# RTC-Power-Eth.net
KiCad netlist of a schematic drawn in Altium Designer
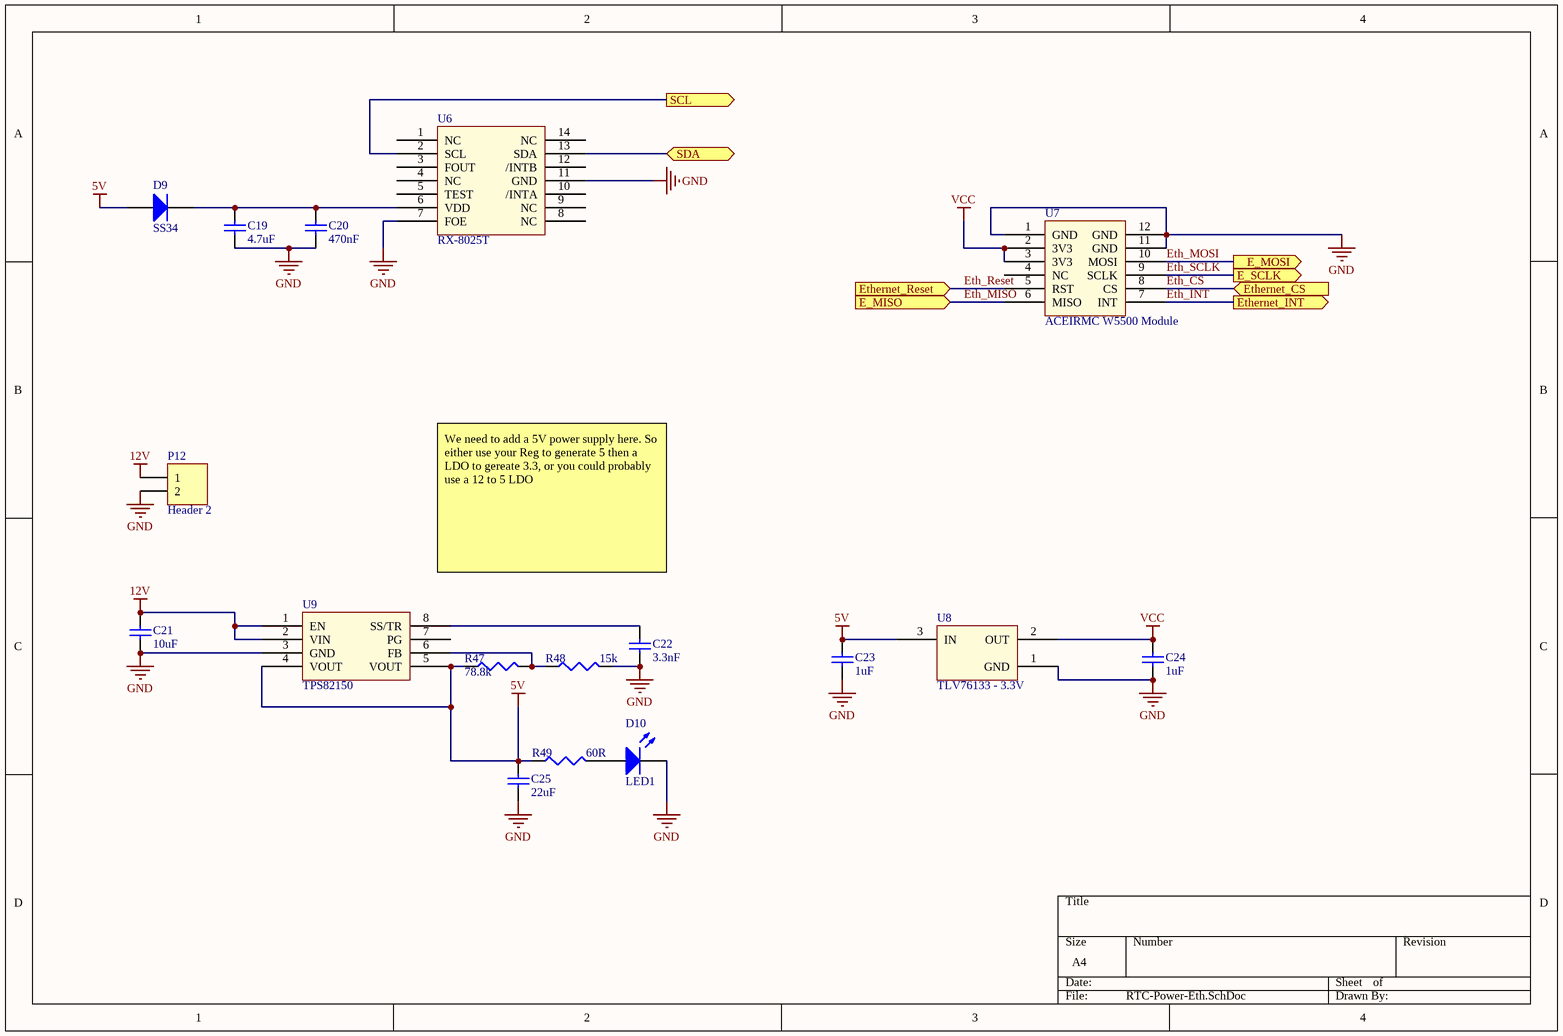
[diagram p0: RTC-Power-Eth.SchDoc]

(export (version "E")
  (design (tool "Eeschema 10.0.6"))
  (components
    (comp (ref "C19")
      (value "4.7uF")
      (footprint "CAPC2012X04M")
      (description "Capacitor")
      (fields (field (name "Comment") "Cap") (field (name "PUBLISHER") "Altium Limited"))
      (libsource (lib "Miscellaneous Devices") (part "Cap"))
    )
    (comp (ref "C20")
      (value "470nF")
      (footprint "CAPC2012X04M")
      (description "Capacitor")
      (fields (field (name "Comment") "Cap") (field (name "PUBLISHER") "Altium Limited"))
      (libsource (lib "Miscellaneous Devices") (part "Cap"))
    )
    (comp (ref "C21")
      (value "10uF")
      (footprint "CAPC2012X04M")
      (description "Capacitor")
      (fields (field (name "Comment") "Cap") (field (name "PUBLISHER") "Altium Limited"))
      (libsource (lib "Miscellaneous Devices") (part "Cap"))
    )
    (comp (ref "C22")
      (value "3.3nF")
      (footprint "CAPC2012X04M")
      (description "Capacitor")
      (fields (field (name "Comment") "Cap") (field (name "PUBLISHER") "Altium Limited"))
      (libsource (lib "Miscellaneous Devices") (part "Cap"))
    )
    (comp (ref "C23")
      (value "1uF")
      (footprint "CAPC2012X04M")
      (description "Capacitor")
      (fields (field (name "Comment") "Cap") (field (name "PUBLISHER") "Altium Limited"))
      (libsource (lib "Miscellaneous Devices") (part "Cap"))
    )
    (comp (ref "C24")
      (value "1uF")
      (footprint "CAPC2012X04M")
      (description "Capacitor")
      (fields (field (name "Comment") "Cap") (field (name "PUBLISHER") "Altium Limited"))
      (libsource (lib "Miscellaneous Devices") (part "Cap"))
    )
    (comp (ref "C25")
      (value "22uF")
      (footprint "CAPC2012X04M")
      (description "Capacitor")
      (fields (field (name "Comment") "Cap") (field (name "PUBLISHER") "Altium Limited"))
      (libsource (lib "Miscellaneous Devices") (part "Cap"))
    )
    (comp (ref "D9")
      (value "SS34")
      (footprint "DIOC2012X04M")
      (description "Default Diode")
      (fields (field (name "PUBLISHER") "Altium Limited"))
      (libsource (lib "Miscellaneous Devices") (part "Diode"))
    )
    (comp (ref "D10")
      (value "LED1")
      (footprint "DIOC2012X04M")
      (description "Typical RED GaAs LED")
      (fields (field (name "PUBLISHER") "Altium Limited"))
      (libsource (lib "Miscellaneous Devices") (part "LED1"))
    )
    (comp (ref "P12")
      (value "Header 2")
      (footprint "WURTH- WR-TBL 2pin 5mmpitch")
      (description "Header, 2-Pin")
      (fields (field (name "PUBLISHER") "Altium Limited"))
      (libsource (lib "Miscellaneous Connectors") (part "Header 2"))
    )
    (comp (ref "R47")
      (value "78.8k")
      (footprint "RESC2012X04M")
      (description "Resistor")
      (fields (field (name "Comment") "Res3") (field (name "PUBLISHER") "Altium Limited"))
      (libsource (lib "Miscellaneous Devices") (part "Res3"))
    )
    (comp (ref "R48")
      (value "15k")
      (footprint "RESC2012X04M")
      (description "Resistor")
      (fields (field (name "Comment") "Res3") (field (name "PUBLISHER") "Altium Limited"))
      (libsource (lib "Miscellaneous Devices") (part "Res3"))
    )
    (comp (ref "R49")
      (value "60R")
      (footprint "RESC2012X04M")
      (description "Resistor")
      (fields (field (name "Comment") "Res3") (field (name "PUBLISHER") "Altium Limited"))
      (libsource (lib "Miscellaneous Devices") (part "Res3"))
    )
    (comp (ref "U6")
      (value "RX-8025T")
      (footprint "SOP127P740X320-14N")
      (libsource (lib "Parts") (part "RX-8025T"))
    )
    (comp (ref "U7")
      (value "ACEIRMC W5500 Module")
      (footprint "W5500Module")
      (libsource (lib "Parts") (part "ACEIRMC W5500 Module"))
    )
    (comp (ref "U8")
      (value "TLV76133 - 3.3V")
      (footprint "SOT230P700X180-4N")
      (libsource (lib "Parts") (part "Generic LDO"))
    )
    (comp (ref "U9") (value "TPS82150") (footprint "TPS82150SIL") (libsource (lib "Parts") (part "TPS82150")))
  )
  (nets
    (net (code "1") (name "/Eth_CS") (class "Default")
      (node (ref "U7") (pin "8") (pinfunction "CS_8") (pintype "passive"))
    )
    (net (code "2") (name "/Eth_INT") (class "Default")
      (node (ref "U7") (pin "7") (pinfunction "INT_7") (pintype "passive"))
    )
    (net (code "3") (name "/Eth_MISO") (class "Default")
      (node (ref "U7") (pin "6") (pinfunction "MISO_6") (pintype "passive"))
    )
    (net (code "4") (name "/Eth_MOSI") (class "Default")
      (node (ref "U7") (pin "10") (pinfunction "MOSI_10") (pintype "passive"))
    )
    (net (code "5") (name "/Eth_Reset") (class "Default")
      (node (ref "U7") (pin "5") (pinfunction "RST_5") (pintype "passive"))
    )
    (net (code "6") (name "/Eth_SCLK") (class "Default")
      (node (ref "U7") (pin "9") (pinfunction "SCLK_9") (pintype "passive"))
    )
    (net (code "7") (name "/SCL") (class "Default")
      (node (ref "U6") (pin "2") (pinfunction "SCL_2") (pintype "passive"))
    )
    (net (code "8") (name "/SDA") (class "Default")
      (node (ref "U6") (pin "13") (pinfunction "SDA_13") (pintype "passive"))
    )
    (net (code "9") (name "5V") (class "Default")
      (node (ref "C23") (pin "1") (pinfunction "1_1") (pintype "passive"))
      (node (ref "C25") (pin "1") (pinfunction "1_1") (pintype "passive"))
      (node (ref "D9") (pin "1") (pinfunction "A_1") (pintype "passive"))
      (node (ref "R47") (pin "1") (pinfunction "1_1") (pintype "passive"))
      (node (ref "R49") (pin "1") (pinfunction "1_1") (pintype "passive"))
      (node (ref "U8") (pin "3") (pinfunction "IN_3") (pintype "passive"))
      (node (ref "U9") (pin "4") (pinfunction "VOUT_4") (pintype "passive"))
      (node (ref "U9") (pin "5") (pinfunction "VOUT_5") (pintype "passive"))
    )
    (net (code "10") (name "12V") (class "Default")
      (node (ref "C21") (pin "1") (pinfunction "1_1") (pintype "passive"))
      (node (ref "P12") (pin "1") (pinfunction "1_1") (pintype "passive"))
      (node (ref "U9") (pin "1") (pinfunction "EN_1") (pintype "passive"))
      (node (ref "U9") (pin "2") (pinfunction "VIN_2") (pintype "passive"))
    )
    (net (code "11") (name "GND") (class "Default")
      (node (ref "C19") (pin "2") (pinfunction "2_2") (pintype "passive"))
      (node (ref "C20") (pin "2") (pinfunction "2_2") (pintype "passive"))
      (node (ref "C21") (pin "2") (pinfunction "2_2") (pintype "passive"))
      (node (ref "C22") (pin "2") (pinfunction "2_2") (pintype "passive"))
      (node (ref "C23") (pin "2") (pinfunction "2_2") (pintype "passive"))
      (node (ref "C24") (pin "2") (pinfunction "2_2") (pintype "passive"))
      (node (ref "C25") (pin "2") (pinfunction "2_2") (pintype "passive"))
      (node (ref "D10") (pin "2") (pinfunction "K_2") (pintype "passive"))
      (node (ref "P12") (pin "2") (pinfunction "2_2") (pintype "passive"))
      (node (ref "R48") (pin "2") (pinfunction "2_2") (pintype "passive"))
      (node (ref "U6") (pin "11") (pinfunction "GND_11") (pintype "passive"))
      (node (ref "U6") (pin "7") (pinfunction "FOE_7") (pintype "passive"))
      (node (ref "U7") (pin "1") (pinfunction "GND_1") (pintype "passive"))
      (node (ref "U7") (pin "11") (pinfunction "GND_11") (pintype "passive"))
      (node (ref "U7") (pin "12") (pinfunction "GND_12") (pintype "passive"))
      (node (ref "U8") (pin "1") (pinfunction "GND_1") (pintype "passive"))
      (node (ref "U9") (pin "3") (pinfunction "GND_3") (pintype "passive"))
    )
    (net (code "12") (name "Net-(D9-K)") (class "Default")
      (node (ref "C19") (pin "1") (pinfunction "1_1") (pintype "passive"))
      (node (ref "C20") (pin "1") (pinfunction "1_1") (pintype "passive"))
      (node (ref "D9") (pin "2") (pinfunction "K_2") (pintype "passive"))
      (node (ref "U6") (pin "6") (pinfunction "VDD_6") (pintype "passive"))
    )
    (net (code "13") (name "Net-(D10-A)") (class "Default")
      (node (ref "D10") (pin "1") (pinfunction "A_1") (pintype "passive"))
      (node (ref "R49") (pin "2") (pinfunction "2_2") (pintype "passive"))
    )
    (net (code "14") (name "Net-(U9-FB)") (class "Default")
      (node (ref "R47") (pin "2") (pinfunction "2_2") (pintype "passive"))
      (node (ref "R48") (pin "1") (pinfunction "1_1") (pintype "passive"))
      (node (ref "U9") (pin "6") (pinfunction "FB_6") (pintype "passive"))
    )
    (net (code "15") (name "Net-(U9-SS{slash}TR)") (class "Default")
      (node (ref "C22") (pin "1") (pinfunction "1_1") (pintype "passive"))
      (node (ref "U9") (pin "8") (pinfunction "SS/TR_8") (pintype "passive"))
    )
    (net (code "16") (name "VCC") (class "Default")
      (node (ref "C24") (pin "1") (pinfunction "1_1") (pintype "passive"))
      (node (ref "U7") (pin "2") (pinfunction "3V3_2") (pintype "passive"))
      (node (ref "U7") (pin "3") (pinfunction "3V3_3") (pintype "passive"))
      (node (ref "U8") (pin "2") (pinfunction "OUT_2") (pintype "passive"))
    )
    (net (code "17") (name "unconnected-(U6-FOUT-Pad3)") (class "Default")
      (node (ref "U6") (pin "3") (pinfunction "FOUT_3") (pintype "passive"))
    )
    (net (code "18") (name "unconnected-(U6-NC-Pad1)") (class "Default")
      (node (ref "U6") (pin "1") (pinfunction "NC_1") (pintype "passive"))
    )
    (net (code "19") (name "unconnected-(U6-NC-Pad4)") (class "Default")
      (node (ref "U6") (pin "4") (pinfunction "NC_4") (pintype "passive"))
    )
    (net (code "20") (name "unconnected-(U6-NC-Pad8)") (class "Default")
      (node (ref "U6") (pin "8") (pinfunction "NC_8") (pintype "passive"))
    )
    (net (code "21") (name "unconnected-(U6-NC-Pad9)") (class "Default")
      (node (ref "U6") (pin "9") (pinfunction "NC_9") (pintype "passive"))
    )
    (net (code "22") (name "unconnected-(U6-NC-Pad14)") (class "Default")
      (node (ref "U6") (pin "14") (pinfunction "NC_14") (pintype "passive"))
    )
    (net (code "23") (name "unconnected-(U6-TEST-Pad5)") (class "Default")
      (node (ref "U6") (pin "5") (pinfunction "TEST_5") (pintype "passive"))
    )
    (net (code "24") (name "unconnected-(U6-{slash}INTA-Pad10)") (class "Default")
      (node (ref "U6") (pin "10") (pinfunction "/INTA_10") (pintype "passive"))
    )
    (net (code "25") (name "unconnected-(U6-{slash}INTB-Pad12)") (class "Default")
      (node (ref "U6") (pin "12") (pinfunction "/INTB_12") (pintype "passive"))
    )
    (net (code "26") (name "unconnected-(U7-NC-Pad4)") (class "Default")
      (node (ref "U7") (pin "4") (pinfunction "NC_4") (pintype "passive"))
    )
    (net (code "27") (name "unconnected-(U9-PG-Pad7)") (class "Default")
      (node (ref "U9") (pin "7") (pinfunction "PG_7") (pintype "passive"))
    )
  )
)
